# 10_ADC.net
KiCad netlist of a schematic drawn in Altium Designer
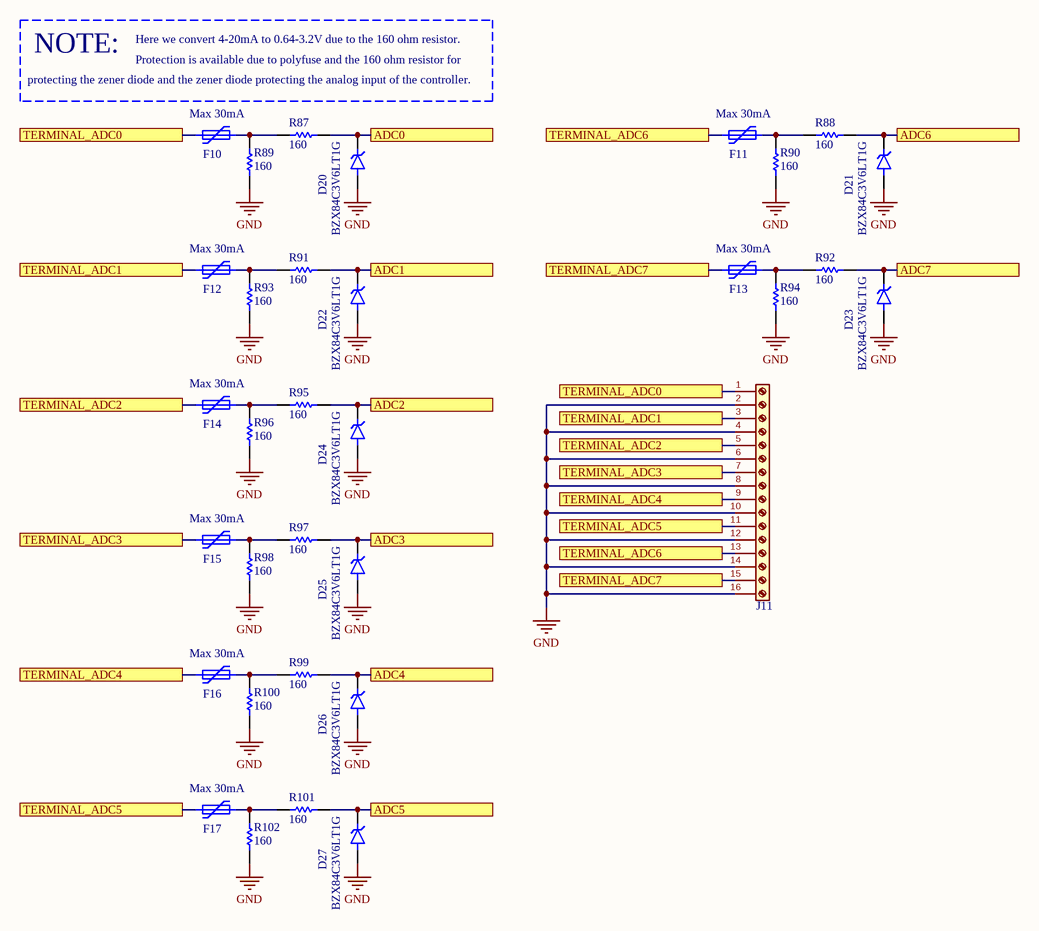
[diagram p0: 10_ADC.SchDoc]

(export (version "E")
  (design (tool "Eeschema 10.0.6"))
  (components
    (comp (ref "D20")
      (value "BZX84C3V6LT1G")
      (footprint "SOT95P240X111-3N")
      (fields (field (name "MP") "BZX84C10LT1G"))
      (libsource (lib "PROC051C_AWR1843BOOST_RevC") (part "BZX84C3V6LT1G"))
    )
    (comp (ref "D21")
      (value "BZX84C3V6LT1G")
      (footprint "SOT95P240X111-3N")
      (fields (field (name "MP") "BZX84C10LT1G"))
      (libsource (lib "PROC051C_AWR1843BOOST_RevC") (part "BZX84C3V6LT1G"))
    )
    (comp (ref "D22")
      (value "BZX84C3V6LT1G")
      (footprint "SOT95P240X111-3N")
      (fields (field (name "MP") "BZX84C10LT1G"))
      (libsource (lib "PROC051C_AWR1843BOOST_RevC") (part "BZX84C3V6LT1G"))
    )
    (comp (ref "D23")
      (value "BZX84C3V6LT1G")
      (footprint "SOT95P240X111-3N")
      (fields (field (name "MP") "BZX84C10LT1G"))
      (libsource (lib "PROC051C_AWR1843BOOST_RevC") (part "BZX84C3V6LT1G"))
    )
    (comp (ref "D24")
      (value "BZX84C3V6LT1G")
      (footprint "SOT95P240X111-3N")
      (fields (field (name "MP") "BZX84C10LT1G"))
      (libsource (lib "PROC051C_AWR1843BOOST_RevC") (part "BZX84C3V6LT1G"))
    )
    (comp (ref "D25")
      (value "BZX84C3V6LT1G")
      (footprint "SOT95P240X111-3N")
      (fields (field (name "MP") "BZX84C10LT1G"))
      (libsource (lib "PROC051C_AWR1843BOOST_RevC") (part "BZX84C3V6LT1G"))
    )
    (comp (ref "D26")
      (value "BZX84C3V6LT1G")
      (footprint "SOT95P240X111-3N")
      (fields (field (name "MP") "BZX84C10LT1G"))
      (libsource (lib "PROC051C_AWR1843BOOST_RevC") (part "BZX84C3V6LT1G"))
    )
    (comp (ref "D27")
      (value "BZX84C3V6LT1G")
      (footprint "SOT95P240X111-3N")
      (fields (field (name "MP") "BZX84C10LT1G"))
      (libsource (lib "PROC051C_AWR1843BOOST_RevC") (part "BZX84C3V6LT1G"))
    )
    (comp (ref "F10")
      (value "Max 30mA")
      (footprint "Fuse_0603_1608Metric")
      (libsource (lib "PROC051C_AWR1843BOOST_RevC") (part "Polyfuse 0603"))
    )
    (comp (ref "F11")
      (value "Max 30mA")
      (footprint "Fuse_0603_1608Metric")
      (libsource (lib "PROC051C_AWR1843BOOST_RevC") (part "Polyfuse 0603"))
    )
    (comp (ref "F12")
      (value "Max 30mA")
      (footprint "Fuse_0603_1608Metric")
      (libsource (lib "PROC051C_AWR1843BOOST_RevC") (part "Polyfuse 0603"))
    )
    (comp (ref "F13")
      (value "Max 30mA")
      (footprint "Fuse_0603_1608Metric")
      (libsource (lib "PROC051C_AWR1843BOOST_RevC") (part "Polyfuse 0603"))
    )
    (comp (ref "F14")
      (value "Max 30mA")
      (footprint "Fuse_0603_1608Metric")
      (libsource (lib "PROC051C_AWR1843BOOST_RevC") (part "Polyfuse 0603"))
    )
    (comp (ref "F15")
      (value "Max 30mA")
      (footprint "Fuse_0603_1608Metric")
      (libsource (lib "PROC051C_AWR1843BOOST_RevC") (part "Polyfuse 0603"))
    )
    (comp (ref "F16")
      (value "Max 30mA")
      (footprint "Fuse_0603_1608Metric")
      (libsource (lib "PROC051C_AWR1843BOOST_RevC") (part "Polyfuse 0603"))
    )
    (comp (ref "F17")
      (value "Max 30mA")
      (footprint "Fuse_0603_1608Metric")
      (libsource (lib "PROC051C_AWR1843BOOST_RevC") (part "Polyfuse 0603"))
    )
    (comp (ref "J11")
      (value "Terminal_01x16_P5.00")
      (footprint "TerminalBlock_Phoenix_PT-1,5-16-5.0-H_1x16_P5.00mm_Horizontal")
      (libsource (lib "PROC051C_AWR1843BOOST_RevC") (part "Terminal_01x16_P5.00"))
    )
    (comp (ref "R87")
      (value "CRCW060320R0JNEA")
      (footprint "0603")
      (description "RES, 160, 5%, 0.1 W, AEC-Q200 Grade 0, 0603")
      (fields (field (name "MANUFACTURER") "Vishay-Dale") (field (name "VALUEDISPLAYED") "160"))
      (libsource (lib "PROC051C_AWR1843BOOST_RevC") (part "RES 160R 0603"))
    )
    (comp (ref "R88")
      (value "CRCW060320R0JNEA")
      (footprint "0603")
      (description "RES, 160, 5%, 0.1 W, AEC-Q200 Grade 0, 0603")
      (fields (field (name "MANUFACTURER") "Vishay-Dale") (field (name "VALUEDISPLAYED") "160"))
      (libsource (lib "PROC051C_AWR1843BOOST_RevC") (part "RES 160R 0603"))
    )
    (comp (ref "R89")
      (value "CRCW060320R0JNEA")
      (footprint "0603")
      (description "RES, 160, 5%, 0.1 W, AEC-Q200 Grade 0, 0603")
      (fields (field (name "MANUFACTURER") "Vishay-Dale") (field (name "VALUEDISPLAYED") "160"))
      (libsource (lib "PROC051C_AWR1843BOOST_RevC") (part "RES 160R 0603"))
    )
    (comp (ref "R90")
      (value "CRCW060320R0JNEA")
      (footprint "0603")
      (description "RES, 160, 5%, 0.1 W, AEC-Q200 Grade 0, 0603")
      (fields (field (name "MANUFACTURER") "Vishay-Dale") (field (name "VALUEDISPLAYED") "160"))
      (libsource (lib "PROC051C_AWR1843BOOST_RevC") (part "RES 160R 0603"))
    )
    (comp (ref "R91")
      (value "CRCW060320R0JNEA")
      (footprint "0603")
      (description "RES, 160, 5%, 0.1 W, AEC-Q200 Grade 0, 0603")
      (fields (field (name "MANUFACTURER") "Vishay-Dale") (field (name "VALUEDISPLAYED") "160"))
      (libsource (lib "PROC051C_AWR1843BOOST_RevC") (part "RES 160R 0603"))
    )
    (comp (ref "R92")
      (value "CRCW060320R0JNEA")
      (footprint "0603")
      (description "RES, 160, 5%, 0.1 W, AEC-Q200 Grade 0, 0603")
      (fields (field (name "MANUFACTURER") "Vishay-Dale") (field (name "VALUEDISPLAYED") "160"))
      (libsource (lib "PROC051C_AWR1843BOOST_RevC") (part "RES 160R 0603"))
    )
    (comp (ref "R93")
      (value "CRCW060320R0JNEA")
      (footprint "0603")
      (description "RES, 160, 5%, 0.1 W, AEC-Q200 Grade 0, 0603")
      (fields (field (name "MANUFACTURER") "Vishay-Dale") (field (name "VALUEDISPLAYED") "160"))
      (libsource (lib "PROC051C_AWR1843BOOST_RevC") (part "RES 160R 0603"))
    )
    (comp (ref "R94")
      (value "CRCW060320R0JNEA")
      (footprint "0603")
      (description "RES, 160, 5%, 0.1 W, AEC-Q200 Grade 0, 0603")
      (fields (field (name "MANUFACTURER") "Vishay-Dale") (field (name "VALUEDISPLAYED") "160"))
      (libsource (lib "PROC051C_AWR1843BOOST_RevC") (part "RES 160R 0603"))
    )
    (comp (ref "R95")
      (value "CRCW060320R0JNEA")
      (footprint "0603")
      (description "RES, 160, 5%, 0.1 W, AEC-Q200 Grade 0, 0603")
      (fields (field (name "MANUFACTURER") "Vishay-Dale") (field (name "VALUEDISPLAYED") "160"))
      (libsource (lib "PROC051C_AWR1843BOOST_RevC") (part "RES 160R 0603"))
    )
    (comp (ref "R96")
      (value "CRCW060320R0JNEA")
      (footprint "0603")
      (description "RES, 160, 5%, 0.1 W, AEC-Q200 Grade 0, 0603")
      (fields (field (name "MANUFACTURER") "Vishay-Dale") (field (name "VALUEDISPLAYED") "160"))
      (libsource (lib "PROC051C_AWR1843BOOST_RevC") (part "RES 160R 0603"))
    )
    (comp (ref "R97")
      (value "CRCW060320R0JNEA")
      (footprint "0603")
      (description "RES, 160, 5%, 0.1 W, AEC-Q200 Grade 0, 0603")
      (fields (field (name "MANUFACTURER") "Vishay-Dale") (field (name "VALUEDISPLAYED") "160"))
      (libsource (lib "PROC051C_AWR1843BOOST_RevC") (part "RES 160R 0603"))
    )
    (comp (ref "R98")
      (value "CRCW060320R0JNEA")
      (footprint "0603")
      (description "RES, 160, 5%, 0.1 W, AEC-Q200 Grade 0, 0603")
      (fields (field (name "MANUFACTURER") "Vishay-Dale") (field (name "VALUEDISPLAYED") "160"))
      (libsource (lib "PROC051C_AWR1843BOOST_RevC") (part "RES 160R 0603"))
    )
    (comp (ref "R99")
      (value "CRCW060320R0JNEA")
      (footprint "0603")
      (description "RES, 160, 5%, 0.1 W, AEC-Q200 Grade 0, 0603")
      (fields (field (name "MANUFACTURER") "Vishay-Dale") (field (name "VALUEDISPLAYED") "160"))
      (libsource (lib "PROC051C_AWR1843BOOST_RevC") (part "RES 160R 0603"))
    )
    (comp (ref "R100")
      (value "CRCW060320R0JNEA")
      (footprint "0603")
      (description "RES, 160, 5%, 0.1 W, AEC-Q200 Grade 0, 0603")
      (fields (field (name "MANUFACTURER") "Vishay-Dale") (field (name "VALUEDISPLAYED") "160"))
      (libsource (lib "PROC051C_AWR1843BOOST_RevC") (part "RES 160R 0603"))
    )
    (comp (ref "R101")
      (value "CRCW060320R0JNEA")
      (footprint "0603")
      (description "RES, 160, 5%, 0.1 W, AEC-Q200 Grade 0, 0603")
      (fields (field (name "MANUFACTURER") "Vishay-Dale") (field (name "VALUEDISPLAYED") "160"))
      (libsource (lib "PROC051C_AWR1843BOOST_RevC") (part "RES 160R 0603"))
    )
    (comp (ref "R102")
      (value "CRCW060320R0JNEA")
      (footprint "0603")
      (description "RES, 160, 5%, 0.1 W, AEC-Q200 Grade 0, 0603")
      (fields (field (name "MANUFACTURER") "Vishay-Dale") (field (name "VALUEDISPLAYED") "160"))
      (libsource (lib "PROC051C_AWR1843BOOST_RevC") (part "RES 160R 0603"))
    )
  )
  (nets
    (net (code "1") (name "/ADC0") (class "Default")
      (node (ref "D20") (pin "3") (pinfunction "K_3") (pintype "passive"))
      (node (ref "R87") (pin "2") (pinfunction "2_2") (pintype "passive"))
    )
    (net (code "2") (name "/ADC1") (class "Default")
      (node (ref "D22") (pin "3") (pinfunction "K_3") (pintype "passive"))
      (node (ref "R91") (pin "2") (pinfunction "2_2") (pintype "passive"))
    )
    (net (code "3") (name "/ADC2") (class "Default")
      (node (ref "D24") (pin "3") (pinfunction "K_3") (pintype "passive"))
      (node (ref "R95") (pin "2") (pinfunction "2_2") (pintype "passive"))
    )
    (net (code "4") (name "/ADC3") (class "Default")
      (node (ref "D25") (pin "3") (pinfunction "K_3") (pintype "passive"))
      (node (ref "R97") (pin "2") (pinfunction "2_2") (pintype "passive"))
    )
    (net (code "5") (name "/ADC4") (class "Default")
      (node (ref "D26") (pin "3") (pinfunction "K_3") (pintype "passive"))
      (node (ref "R99") (pin "2") (pinfunction "2_2") (pintype "passive"))
    )
    (net (code "6") (name "/ADC5") (class "Default")
      (node (ref "D27") (pin "3") (pinfunction "K_3") (pintype "passive"))
      (node (ref "R101") (pin "2") (pinfunction "2_2") (pintype "passive"))
    )
    (net (code "7") (name "/ADC6") (class "Default")
      (node (ref "D21") (pin "3") (pinfunction "K_3") (pintype "passive"))
      (node (ref "R88") (pin "2") (pinfunction "2_2") (pintype "passive"))
    )
    (net (code "8") (name "/ADC7") (class "Default")
      (node (ref "D23") (pin "3") (pinfunction "K_3") (pintype "passive"))
      (node (ref "R92") (pin "2") (pinfunction "2_2") (pintype "passive"))
    )
    (net (code "9") (name "/TERMINAL_ADC0") (class "Default")
      (node (ref "F10") (pin "1") (pinfunction "1_1") (pintype "passive"))
      (node (ref "J11") (pin "1") (pinfunction "Pin_1_1") (pintype "passive"))
    )
    (net (code "10") (name "/TERMINAL_ADC1") (class "Default")
      (node (ref "F12") (pin "1") (pinfunction "1_1") (pintype "passive"))
      (node (ref "J11") (pin "3") (pinfunction "Pin_3_3") (pintype "passive"))
    )
    (net (code "11") (name "/TERMINAL_ADC2") (class "Default")
      (node (ref "F14") (pin "1") (pinfunction "1_1") (pintype "passive"))
      (node (ref "J11") (pin "5") (pinfunction "Pin_5_5") (pintype "passive"))
    )
    (net (code "12") (name "/TERMINAL_ADC3") (class "Default")
      (node (ref "F15") (pin "1") (pinfunction "1_1") (pintype "passive"))
      (node (ref "J11") (pin "7") (pinfunction "Pin_7_7") (pintype "passive"))
    )
    (net (code "13") (name "/TERMINAL_ADC4") (class "Default")
      (node (ref "F16") (pin "1") (pinfunction "1_1") (pintype "passive"))
      (node (ref "J11") (pin "9") (pinfunction "Pin_9_9") (pintype "passive"))
    )
    (net (code "14") (name "/TERMINAL_ADC5") (class "Default")
      (node (ref "F17") (pin "1") (pinfunction "1_1") (pintype "passive"))
      (node (ref "J11") (pin "11") (pinfunction "Pin_11_11") (pintype "passive"))
    )
    (net (code "15") (name "/TERMINAL_ADC6") (class "Default")
      (node (ref "F11") (pin "1") (pinfunction "1_1") (pintype "passive"))
      (node (ref "J11") (pin "13") (pinfunction "Pin_13_13") (pintype "passive"))
    )
    (net (code "16") (name "/TERMINAL_ADC7") (class "Default")
      (node (ref "F13") (pin "1") (pinfunction "1_1") (pintype "passive"))
      (node (ref "J11") (pin "15") (pinfunction "Pin_15_15") (pintype "passive"))
    )
    (net (code "17") (name "GND") (class "Default")
      (node (ref "D20") (pin "1") (pinfunction "A_1") (pintype "passive"))
      (node (ref "D21") (pin "1") (pinfunction "A_1") (pintype "passive"))
      (node (ref "D22") (pin "1") (pinfunction "A_1") (pintype "passive"))
      (node (ref "D23") (pin "1") (pinfunction "A_1") (pintype "passive"))
      (node (ref "D24") (pin "1") (pinfunction "A_1") (pintype "passive"))
      (node (ref "D25") (pin "1") (pinfunction "A_1") (pintype "passive"))
      (node (ref "D26") (pin "1") (pinfunction "A_1") (pintype "passive"))
      (node (ref "D27") (pin "1") (pinfunction "A_1") (pintype "passive"))
      (node (ref "J11") (pin "10") (pinfunction "Pin_10_10") (pintype "passive"))
      (node (ref "J11") (pin "12") (pinfunction "Pin_12_12") (pintype "passive"))
      (node (ref "J11") (pin "14") (pinfunction "Pin_14_14") (pintype "passive"))
      (node (ref "J11") (pin "16") (pinfunction "Pin_16_16") (pintype "passive"))
      (node (ref "J11") (pin "2") (pinfunction "Pin_2_2") (pintype "passive"))
      (node (ref "J11") (pin "4") (pinfunction "Pin_4_4") (pintype "passive"))
      (node (ref "J11") (pin "6") (pinfunction "Pin_6_6") (pintype "passive"))
      (node (ref "J11") (pin "8") (pinfunction "Pin_8_8") (pintype "passive"))
      (node (ref "R100") (pin "1") (pinfunction "1_1") (pintype "passive"))
      (node (ref "R102") (pin "1") (pinfunction "1_1") (pintype "passive"))
      (node (ref "R89") (pin "1") (pinfunction "1_1") (pintype "passive"))
      (node (ref "R90") (pin "1") (pinfunction "1_1") (pintype "passive"))
      (node (ref "R93") (pin "1") (pinfunction "1_1") (pintype "passive"))
      (node (ref "R94") (pin "1") (pinfunction "1_1") (pintype "passive"))
      (node (ref "R96") (pin "1") (pinfunction "1_1") (pintype "passive"))
      (node (ref "R98") (pin "1") (pinfunction "1_1") (pintype "passive"))
    )
    (net (code "18") (name "Net-(F10-Pad2)") (class "Default")
      (node (ref "F10") (pin "2") (pinfunction "2_2") (pintype "passive"))
      (node (ref "R87") (pin "1") (pinfunction "1_1") (pintype "passive"))
      (node (ref "R89") (pin "2") (pinfunction "2_2") (pintype "passive"))
    )
    (net (code "19") (name "Net-(F11-Pad2)") (class "Default")
      (node (ref "F11") (pin "2") (pinfunction "2_2") (pintype "passive"))
      (node (ref "R88") (pin "1") (pinfunction "1_1") (pintype "passive"))
      (node (ref "R90") (pin "2") (pinfunction "2_2") (pintype "passive"))
    )
    (net (code "20") (name "Net-(F12-Pad2)") (class "Default")
      (node (ref "F12") (pin "2") (pinfunction "2_2") (pintype "passive"))
      (node (ref "R91") (pin "1") (pinfunction "1_1") (pintype "passive"))
      (node (ref "R93") (pin "2") (pinfunction "2_2") (pintype "passive"))
    )
    (net (code "21") (name "Net-(F13-Pad2)") (class "Default")
      (node (ref "F13") (pin "2") (pinfunction "2_2") (pintype "passive"))
      (node (ref "R92") (pin "1") (pinfunction "1_1") (pintype "passive"))
      (node (ref "R94") (pin "2") (pinfunction "2_2") (pintype "passive"))
    )
    (net (code "22") (name "Net-(F14-Pad2)") (class "Default")
      (node (ref "F14") (pin "2") (pinfunction "2_2") (pintype "passive"))
      (node (ref "R95") (pin "1") (pinfunction "1_1") (pintype "passive"))
      (node (ref "R96") (pin "2") (pinfunction "2_2") (pintype "passive"))
    )
    (net (code "23") (name "Net-(F15-Pad2)") (class "Default")
      (node (ref "F15") (pin "2") (pinfunction "2_2") (pintype "passive"))
      (node (ref "R97") (pin "1") (pinfunction "1_1") (pintype "passive"))
      (node (ref "R98") (pin "2") (pinfunction "2_2") (pintype "passive"))
    )
    (net (code "24") (name "Net-(F16-Pad2)") (class "Default")
      (node (ref "F16") (pin "2") (pinfunction "2_2") (pintype "passive"))
      (node (ref "R100") (pin "2") (pinfunction "2_2") (pintype "passive"))
      (node (ref "R99") (pin "1") (pinfunction "1_1") (pintype "passive"))
    )
    (net (code "25") (name "Net-(F17-Pad2)") (class "Default")
      (node (ref "F17") (pin "2") (pinfunction "2_2") (pintype "passive"))
      (node (ref "R101") (pin "1") (pinfunction "1_1") (pintype "passive"))
      (node (ref "R102") (pin "2") (pinfunction "2_2") (pintype "passive"))
    )
  )
)
